# 30_Pin_Breakout_v1.net
KiCad netlist of a schematic drawn in EAGLE
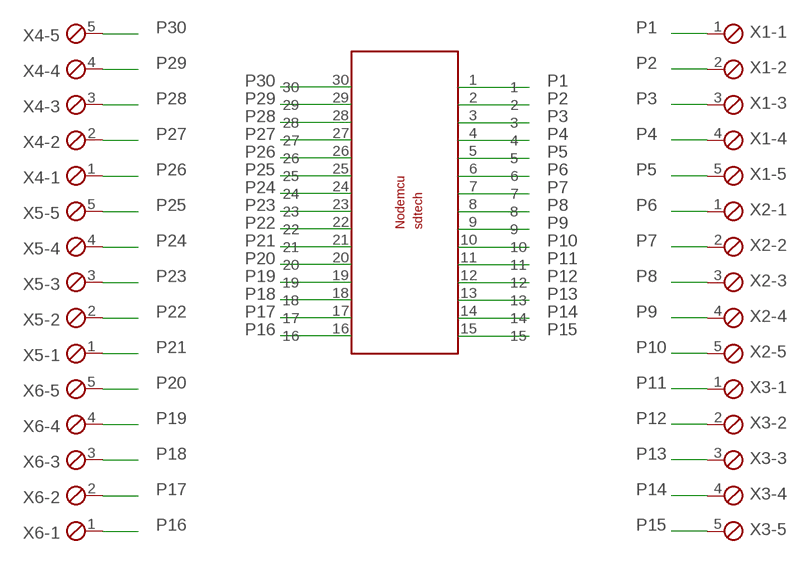
[diagram p0: schematic, sheet 1]

(export (version "E")
  (design (tool "Eeschema 10.0.6"))
  (components
    (comp (ref "U$1")
      (value "NODEMCUESP8266")
      (footprint "eagle-import:NODEMCUESP8266")
      (libsource (lib "eagle-import") (part "NODEMCUESP8266"))
    )
    (comp (ref "X1")
      (value "MPT5")
      (footprint "eagle-import:5POL254")
      (libsource (lib "eagle-import") (part "MPT5"))
    )
    (comp (ref "X2")
      (value "MPT5")
      (footprint "eagle-import:5POL254")
      (libsource (lib "eagle-import") (part "MPT5"))
    )
    (comp (ref "X3")
      (value "MPT5")
      (footprint "eagle-import:5POL254")
      (libsource (lib "eagle-import") (part "MPT5"))
    )
    (comp (ref "X4")
      (value "MPT5")
      (footprint "eagle-import:5POL254")
      (libsource (lib "eagle-import") (part "MPT5"))
    )
    (comp (ref "X5")
      (value "MPT5")
      (footprint "eagle-import:5POL254")
      (libsource (lib "eagle-import") (part "MPT5"))
    )
    (comp (ref "X6")
      (value "MPT5")
      (footprint "eagle-import:5POL254")
      (libsource (lib "eagle-import") (part "MPT5"))
    )
  )
  (nets
    (net (code "1") (name "/P1") (class "Default")
      (node (ref "U$1") (pin "1") (pinfunction "1_1") (pintype "bidirectional"))
      (node (ref "X1") (pin "1") (pinfunction "1_1") (pintype "passive"))
    )
    (net (code "2") (name "/P2") (class "Default")
      (node (ref "U$1") (pin "2") (pinfunction "2_2") (pintype "bidirectional"))
      (node (ref "X1") (pin "2") (pinfunction "1_2") (pintype "passive"))
    )
    (net (code "3") (name "/P3") (class "Default")
      (node (ref "U$1") (pin "3") (pinfunction "3_3") (pintype "bidirectional"))
      (node (ref "X1") (pin "3") (pinfunction "1_3") (pintype "passive"))
    )
    (net (code "4") (name "/P4") (class "Default")
      (node (ref "U$1") (pin "4") (pinfunction "4_4") (pintype "bidirectional"))
      (node (ref "X1") (pin "4") (pinfunction "1_4") (pintype "passive"))
    )
    (net (code "5") (name "/P5") (class "Default")
      (node (ref "U$1") (pin "5") (pinfunction "5_5") (pintype "bidirectional"))
      (node (ref "X1") (pin "5") (pinfunction "1_5") (pintype "passive"))
    )
    (net (code "6") (name "/P6") (class "Default")
      (node (ref "U$1") (pin "6") (pinfunction "6_6") (pintype "bidirectional"))
      (node (ref "X2") (pin "1") (pinfunction "1_1") (pintype "passive"))
    )
    (net (code "7") (name "/P7") (class "Default")
      (node (ref "U$1") (pin "7") (pinfunction "7_7") (pintype "bidirectional"))
      (node (ref "X2") (pin "2") (pinfunction "1_2") (pintype "passive"))
    )
    (net (code "8") (name "/P8") (class "Default")
      (node (ref "U$1") (pin "8") (pinfunction "8_8") (pintype "bidirectional"))
      (node (ref "X2") (pin "3") (pinfunction "1_3") (pintype "passive"))
    )
    (net (code "9") (name "/P9") (class "Default")
      (node (ref "U$1") (pin "9") (pinfunction "9_9") (pintype "bidirectional"))
      (node (ref "X2") (pin "4") (pinfunction "1_4") (pintype "passive"))
    )
    (net (code "10") (name "/P10") (class "Default")
      (node (ref "U$1") (pin "10") (pinfunction "10_10") (pintype "bidirectional"))
      (node (ref "X2") (pin "5") (pinfunction "1_5") (pintype "passive"))
    )
    (net (code "11") (name "/P11") (class "Default")
      (node (ref "U$1") (pin "11") (pinfunction "11_11") (pintype "bidirectional"))
      (node (ref "X3") (pin "1") (pinfunction "1_1") (pintype "passive"))
    )
    (net (code "12") (name "/P12") (class "Default")
      (node (ref "U$1") (pin "12") (pinfunction "12_12") (pintype "bidirectional"))
      (node (ref "X3") (pin "2") (pinfunction "1_2") (pintype "passive"))
    )
    (net (code "13") (name "/P13") (class "Default")
      (node (ref "U$1") (pin "13") (pinfunction "13_13") (pintype "bidirectional"))
      (node (ref "X3") (pin "3") (pinfunction "1_3") (pintype "passive"))
    )
    (net (code "14") (name "/P14") (class "Default")
      (node (ref "U$1") (pin "14") (pinfunction "14_14") (pintype "bidirectional"))
      (node (ref "X3") (pin "4") (pinfunction "1_4") (pintype "passive"))
    )
    (net (code "15") (name "/P15") (class "Default")
      (node (ref "U$1") (pin "15") (pinfunction "15_15") (pintype "bidirectional"))
      (node (ref "X3") (pin "5") (pinfunction "1_5") (pintype "passive"))
    )
    (net (code "16") (name "/P16") (class "Default")
      (node (ref "U$1") (pin "16") (pinfunction "16_16") (pintype "bidirectional"))
      (node (ref "X6") (pin "1") (pinfunction "1_1") (pintype "passive"))
    )
    (net (code "17") (name "/P17") (class "Default")
      (node (ref "U$1") (pin "17") (pinfunction "17_17") (pintype "bidirectional"))
      (node (ref "X6") (pin "2") (pinfunction "1_2") (pintype "passive"))
    )
    (net (code "18") (name "/P18") (class "Default")
      (node (ref "U$1") (pin "18") (pinfunction "18_18") (pintype "bidirectional"))
      (node (ref "X6") (pin "3") (pinfunction "1_3") (pintype "passive"))
    )
    (net (code "19") (name "/P19") (class "Default")
      (node (ref "U$1") (pin "19") (pinfunction "19_19") (pintype "bidirectional"))
      (node (ref "X6") (pin "4") (pinfunction "1_4") (pintype "passive"))
    )
    (net (code "20") (name "/P20") (class "Default")
      (node (ref "U$1") (pin "20") (pinfunction "20_20") (pintype "bidirectional"))
      (node (ref "X6") (pin "5") (pinfunction "1_5") (pintype "passive"))
    )
    (net (code "21") (name "/P21") (class "Default")
      (node (ref "U$1") (pin "21") (pinfunction "21_21") (pintype "bidirectional"))
      (node (ref "X5") (pin "1") (pinfunction "1_1") (pintype "passive"))
    )
    (net (code "22") (name "/P22") (class "Default")
      (node (ref "U$1") (pin "22") (pinfunction "22_22") (pintype "bidirectional"))
      (node (ref "X5") (pin "2") (pinfunction "1_2") (pintype "passive"))
    )
    (net (code "23") (name "/P23") (class "Default")
      (node (ref "U$1") (pin "23") (pinfunction "23_23") (pintype "bidirectional"))
      (node (ref "X5") (pin "3") (pinfunction "1_3") (pintype "passive"))
    )
    (net (code "24") (name "/P24") (class "Default")
      (node (ref "U$1") (pin "24") (pinfunction "24_24") (pintype "bidirectional"))
      (node (ref "X5") (pin "4") (pinfunction "1_4") (pintype "passive"))
    )
    (net (code "25") (name "/P25") (class "Default")
      (node (ref "U$1") (pin "25") (pinfunction "25_25") (pintype "bidirectional"))
      (node (ref "X5") (pin "5") (pinfunction "1_5") (pintype "passive"))
    )
    (net (code "26") (name "/P26") (class "Default")
      (node (ref "U$1") (pin "26") (pinfunction "26_26") (pintype "bidirectional"))
      (node (ref "X4") (pin "1") (pinfunction "1_1") (pintype "passive"))
    )
    (net (code "27") (name "/P27") (class "Default")
      (node (ref "U$1") (pin "27") (pinfunction "27_27") (pintype "bidirectional"))
      (node (ref "X4") (pin "2") (pinfunction "1_2") (pintype "passive"))
    )
    (net (code "28") (name "/P28") (class "Default")
      (node (ref "U$1") (pin "28") (pinfunction "28_28") (pintype "bidirectional"))
      (node (ref "X4") (pin "3") (pinfunction "1_3") (pintype "passive"))
    )
    (net (code "29") (name "/P29") (class "Default")
      (node (ref "U$1") (pin "29") (pinfunction "29_29") (pintype "bidirectional"))
      (node (ref "X4") (pin "4") (pinfunction "1_4") (pintype "passive"))
    )
    (net (code "30") (name "/P30") (class "Default")
      (node (ref "U$1") (pin "30") (pinfunction "30_30") (pintype "bidirectional"))
      (node (ref "X4") (pin "5") (pinfunction "1_5") (pintype "passive"))
    )
  )
)
